# SCH_VRegulator_2024-07-16.net
KiCad netlist of a schematic drawn in EasyEDA
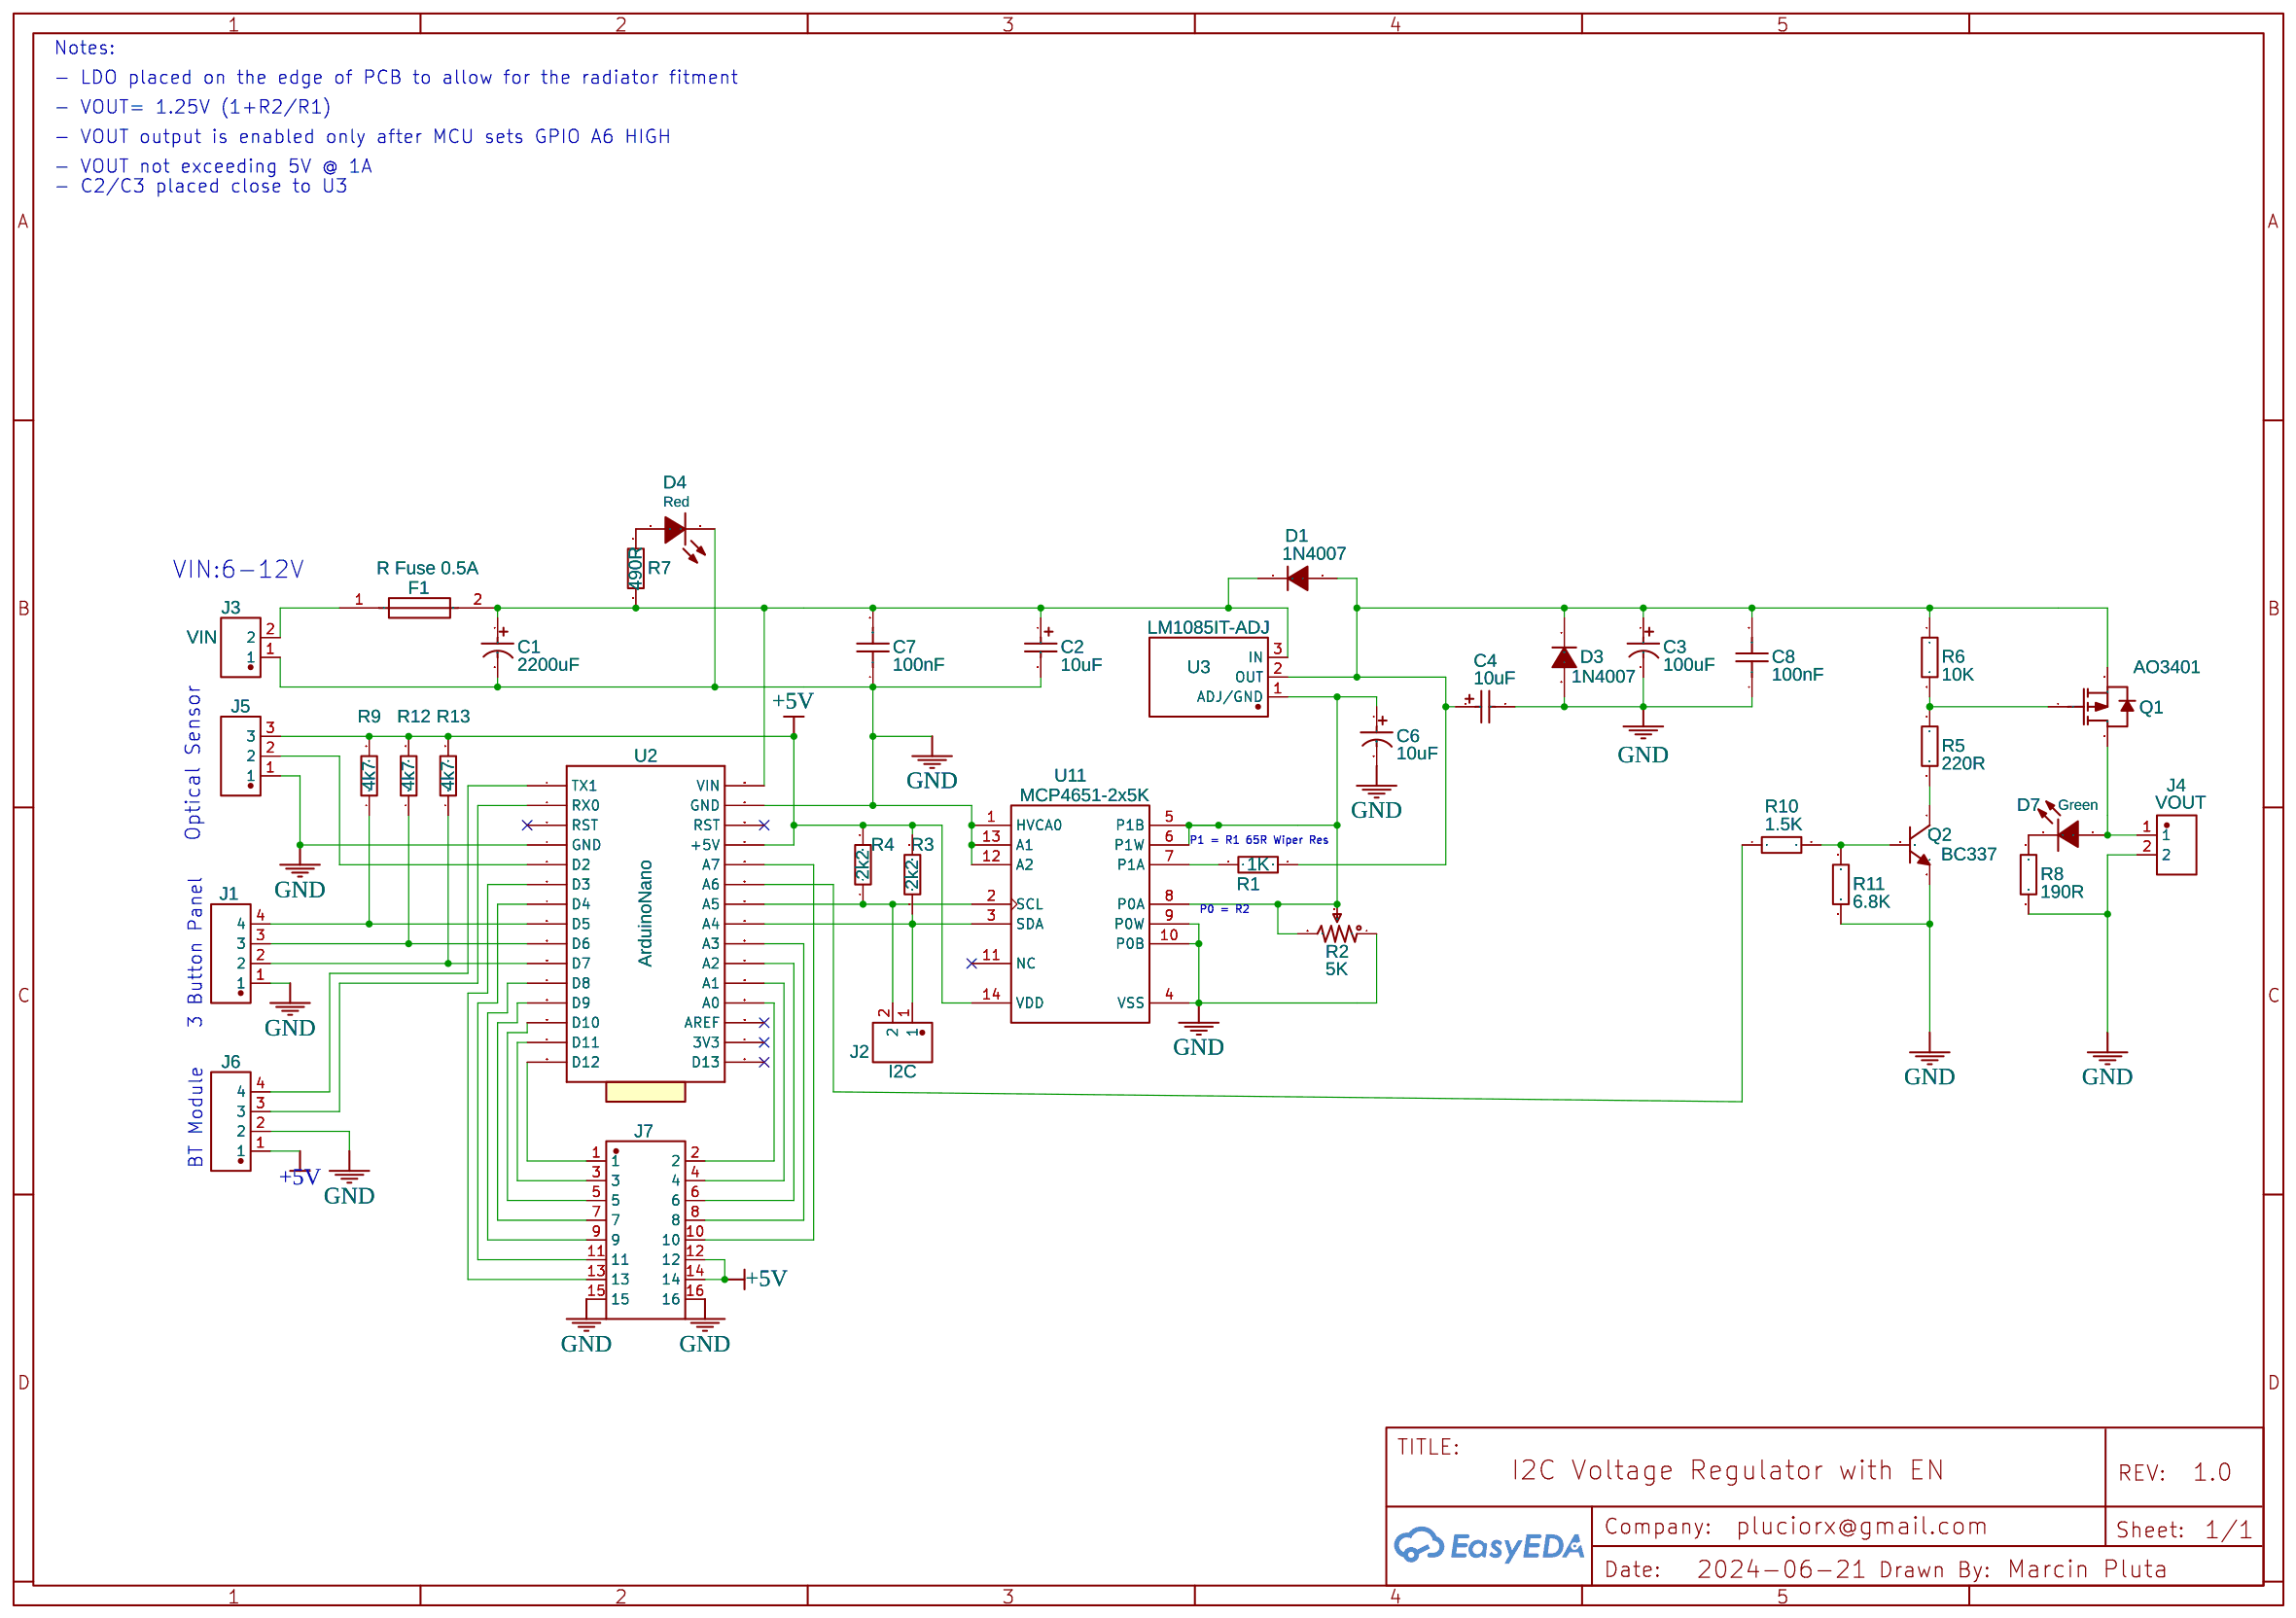
[diagram p0: schematic sheet]

(export (version "E")
  (design (tool "Eeschema 10.0.6"))
  (components
    (comp (ref "C1")
      (value "2200uF")
      (fields
        (field (name "Manufacturer Part") "KM228M025J20RR0VH2FP0")
        (field (name "Manufacturer") "CX(承兴)")
      )
      (libsource (lib "") (part "2200uF 25V 13*20"))
    )
    (comp (ref "C2")
      (value "10uF")
      (fields (field (name "Manufacturer Part") "TAJC106K025RNJ") (field (name "Manufacturer") "Kyocera AVX"))
      (libsource (lib "") (part "TAJC106K025RNJ_1"))
    )
    (comp (ref "C3")
      (value "100uF")
      (fields (field (name "Manufacturer Part") "ERS1EM101E11OT") (field (name "Manufacturer") "AISHI(艾华集团)"))
      (libsource (lib "") (part "ERS1EM101E11OT"))
    )
    (comp (ref "C4")
      (value "10uF")
      (fields (field (name "Manufacturer Part") "TAJC106K025RNJ") (field (name "Manufacturer") "Kyocera AVX"))
      (libsource (lib "") (part "TAJC106K025RNJ"))
    )
    (comp (ref "C6")
      (value "10uF")
      (fields (field (name "Manufacturer Part") "KF100M025C110A") (field (name "Manufacturer") "CapXon(丰宾)"))
      (libsource (lib "") (part "KF100M025C110A"))
    )
    (comp (ref "C7")
      (value "100nF")
      (fields
        (field (name "Manufacturer Part") "CC2A104ZC1ED3F7C1100")
        (field (name "Manufacturer") "Dersonic(德尔创)")
      )
      (libsource (lib "") (part "CC2A104ZC1ED3F7C1100"))
    )
    (comp (ref "C8")
      (value "100nF")
      (fields
        (field (name "Manufacturer Part") "CC2A104ZC1ED3F7C1100")
        (field (name "Manufacturer") "Dersonic(德尔创)")
      )
      (libsource (lib "") (part "CC2A104ZC1ED3F7C1100"))
    )
    (comp (ref "D1")
      (value "1N4007")
      (fields (field (name "Manufacturer") "DYELEC"))
      (libsource (lib "") (part "1N4007_C84179_1"))
    )
    (comp (ref "D3")
      (value "1N4007")
      (fields (field (name "Manufacturer") "DYELEC"))
      (libsource (lib "") (part "1N4007_C84179"))
    )
    (comp (ref "D4")
      (value "Red")
      (fields (field (name "Manufacturer Part") "WP710A10ID") (field (name "Manufacturer") "Kingbright"))
      (libsource (lib "") (part "WP710A10ID"))
    )
    (comp (ref "D7")
      (value "Green")
      (fields (field (name "Manufacturer Part") "WP710A10ID") (field (name "Manufacturer") "Kingbright"))
      (libsource (lib "") (part "WP710A10ID_1"))
    )
    (comp (ref "F1")
      (value "R Fuse 0.5A")
      (fields (field (name "Manufacturer Part") "ResettableFuse-500mA"))
      (libsource (lib "") (part "RESETTABLEFUSE-500MA"))
    )
    (comp (ref "J1")
      (value "DZ254W-11-04-65")
      (fields (field (name "Manufacturer") "DEALON(德艺隆)"))
      (libsource (lib "") (part "DZ254W-11-04-65"))
    )
    (comp (ref "J2")
      (value "I2C")
      (fields
        (field (name "Manufacturer Part") "DB301V-3.5-2P-GN-S")
        (field (name "Manufacturer") "DORABO(地博电气)")
      )
      (libsource (lib "") (part "DB301V-3.5-2P-GN_2"))
    )
    (comp (ref "J3")
      (value "VIN")
      (fields
        (field (name "Manufacturer Part") "DB301V-3.5-2P-GN-S")
        (field (name "Manufacturer") "DORABO(地博电气)")
      )
      (libsource (lib "") (part "DB301V-3.5-2P-GN"))
    )
    (comp (ref "J4")
      (value "VOUT")
      (fields
        (field (name "Manufacturer Part") "DB301V-3.5-2P-GN-S")
        (field (name "Manufacturer") "DORABO(地博电气)")
      )
      (libsource (lib "") (part "DB301V-3.5-2P-GN_1"))
    )
    (comp (ref "J5")
      (value "J5")
      (fields
        (field (name "Manufacturer Part") "DB301V-3.5-3P-GN-S")
        (field (name "Manufacturer") "DORABO(地博电气)")
      )
      (libsource (lib "") (part "DB301V-3.5-3P-GN"))
    )
    (comp (ref "J6")
      (value "A2541HWV-4P_C5176037")
      (fields (field (name "Manufacturer Part") "A2541HWV-4P") (field (name "Manufacturer") "CJT(长江连接器)"))
      (libsource (lib "") (part "A2541HWV-4P_C5176037"))
    )
    (comp (ref "J7")
      (value "MZ254R-22-16-10")
      (fields (field (name "Manufacturer") "DEALON(德艺隆)"))
      (libsource (lib "") (part "MZ254R-22-16-10"))
    )
    (comp (ref "Q1")
      (value "AO3401")
      (fields (field (name "Manufacturer") "YFW(佑风微)"))
      (libsource (lib "") (part "AO3401_C2977510"))
    )
    (comp (ref "Q2")
      (value "BC337")
      (fields (field (name "Manufacturer Part") "BC33740BU") (field (name "Manufacturer") "onsemi(安森美)"))
      (libsource (lib "") (part "BC33740BU"))
    )
    (comp (ref "R1")
      (value "1K")
      (fields (field (name "Manufacturer Part") "MOR01SJ0101A10") (field (name "Manufacturer") "Multicomp"))
      (libsource (lib "") (part "RESISTOR 100 OHM 1W COPY_1"))
    )
    (comp (ref "R2")
      (value "5K")
      (fields (field (name "Manufacturer Part") "3296W-1-502") (field (name "Manufacturer") "BOCHEN(博晨)"))
      (libsource (lib "") (part "3296W-1-502"))
    )
    (comp (ref "R3")
      (value "2k2")
      (fields (field (name "Manufacturer Part") "MOR01SJ0101A10") (field (name "Manufacturer") "Multicomp"))
      (libsource (lib "") (part "RESISTOR 100 OHM 1W COPY"))
    )
    (comp (ref "R4")
      (value "2k2")
      (fields (field (name "Manufacturer Part") "MOR01SJ0101A10") (field (name "Manufacturer") "Multicomp"))
      (libsource (lib "") (part "RESISTOR 100 OHM 1W COPY"))
    )
    (comp (ref "R5")
      (value "220R")
      (fields (field (name "Manufacturer Part") "MOR01SJ0101A10") (field (name "Manufacturer") "Multicomp"))
      (libsource (lib "") (part "RESISTOR 100 OHM 1W COPY_2"))
    )
    (comp (ref "R6")
      (value "10K")
      (fields (field (name "Manufacturer Part") "MOR01SJ0101A10") (field (name "Manufacturer") "Multicomp"))
      (libsource (lib "") (part "RESISTOR 100 OHM 1W COPY_2"))
    )
    (comp (ref "R7")
      (value "490R")
      (fields (field (name "Manufacturer Part") "MOR01SJ0101A10") (field (name "Manufacturer") "Multicomp"))
      (libsource (lib "") (part "RESISTOR 100 OHM 1W COPY_2"))
    )
    (comp (ref "R8")
      (value "190R")
      (fields (field (name "Manufacturer Part") "MOR01SJ0101A10") (field (name "Manufacturer") "Multicomp"))
      (libsource (lib "") (part "RESISTOR 100 OHM 1W COPY_2"))
    )
    (comp (ref "R9")
      (value "4k7")
      (fields (field (name "Manufacturer Part") "MOR01SJ0101A10") (field (name "Manufacturer") "Multicomp"))
      (libsource (lib "") (part "RESISTOR 100 OHM 1W COPY"))
    )
    (comp (ref "R10")
      (value "1.5K")
      (fields (field (name "Manufacturer Part") "MOR01SJ0101A10") (field (name "Manufacturer") "Multicomp"))
      (libsource (lib "") (part "RESISTOR 100 OHM 1W COPY_3"))
    )
    (comp (ref "R11")
      (value "6.8K")
      (fields (field (name "Manufacturer Part") "MOR01SJ0101A10") (field (name "Manufacturer") "Multicomp"))
      (libsource (lib "") (part "RESISTOR 100 OHM 1W COPY"))
    )
    (comp (ref "R12")
      (value "4k7")
      (fields (field (name "Manufacturer Part") "MOR01SJ0101A10") (field (name "Manufacturer") "Multicomp"))
      (libsource (lib "") (part "RESISTOR 100 OHM 1W COPY"))
    )
    (comp (ref "R13")
      (value "4k7")
      (fields (field (name "Manufacturer Part") "MOR01SJ0101A10") (field (name "Manufacturer") "Multicomp"))
      (libsource (lib "") (part "RESISTOR 100 OHM 1W COPY"))
    )
    (comp (ref "U2") (value "ArduinoNano") (libsource (lib "") (part "ArduinoNano_FIX")))
    (comp (ref "U3")
      (value "LM1085IT-ADJ")
      (fields (field (name "Manufacturer Part") "LM1085IT-ADJG") (field (name "Manufacturer") "HGC(深圳汉芯)"))
      (libsource (lib "") (part "LM1085IT-ADJG"))
    )
    (comp (ref "U11")
      (value "MCP4651-2x5K")
      (fields
        (field (name "Manufacturer Part") "MCP4651-103E/ST")
        (field (name "Manufacturer") "MICROCHIP(美国微芯)")
      )
      (libsource (lib "") (part "MCP4651-103E/ST"))
    )
  )
  (nets
    (net (code "1") (name "+5V") (class "Default")
      (node (ref "J5") (pin "3") (pinfunction "3_3") (pintype "unspecified"))
      (node (ref "J6") (pin "1") (pinfunction "1_1") (pintype "unspecified"))
      (node (ref "J7") (pin "12") (pinfunction "12_12") (pintype "unspecified"))
      (node (ref "J7") (pin "14") (pinfunction "14_14") (pintype "unspecified"))
      (node (ref "R12") (pin "2") (pinfunction "2_2") (pintype "unspecified"))
      (node (ref "R13") (pin "2") (pinfunction "2_2") (pintype "unspecified"))
      (node (ref "R3") (pin "2") (pinfunction "2_2") (pintype "unspecified"))
      (node (ref "R4") (pin "2") (pinfunction "2_2") (pintype "unspecified"))
      (node (ref "R9") (pin "2") (pinfunction "2_2") (pintype "unspecified"))
      (node (ref "U11") (pin "14") (pinfunction "VDD_14") (pintype "passive"))
      (node (ref "U2") (pin "27") (pinfunction "+5V_27") (pintype "passive"))
    )
    (net (code "2") (name "GND") (class "Default")
      (node (ref "C1") (pin "2") (pinfunction "2_2") (pintype "input"))
      (node (ref "C2") (pin "2") (pinfunction "2_2") (pintype "input"))
      (node (ref "C3") (pin "2") (pinfunction "2_2") (pintype "input"))
      (node (ref "C4") (pin "2") (pinfunction "2_2") (pintype "input"))
      (node (ref "C6") (pin "2") (pinfunction "2_2") (pintype "input"))
      (node (ref "C7") (pin "1") (pinfunction "1_1") (pintype "unspecified"))
      (node (ref "C8") (pin "1") (pinfunction "1_1") (pintype "unspecified"))
      (node (ref "D3") (pin "2") (pinfunction "A_2") (pintype "unspecified"))
      (node (ref "D4") (pin "2") (pinfunction "K_2") (pintype "unspecified"))
      (node (ref "J1") (pin "1") (pinfunction "1_1") (pintype "unspecified"))
      (node (ref "J3") (pin "1") (pinfunction "1_1") (pintype "unspecified"))
      (node (ref "J4") (pin "2") (pinfunction "2_2") (pintype "unspecified"))
      (node (ref "J5") (pin "1") (pinfunction "1_1") (pintype "unspecified"))
      (node (ref "J6") (pin "2") (pinfunction "2_2") (pintype "unspecified"))
      (node (ref "J7") (pin "15") (pinfunction "15_15") (pintype "unspecified"))
      (node (ref "J7") (pin "16") (pinfunction "16_16") (pintype "unspecified"))
      (node (ref "Q2") (pin "3") (pinfunction "E_3") (pintype "input"))
      (node (ref "R11") (pin "1") (pinfunction "1_1") (pintype "unspecified"))
      (node (ref "R2") (pin "1") (pinfunction "1_1") (pintype "unspecified"))
      (node (ref "R8") (pin "2") (pinfunction "2_2") (pintype "unspecified"))
      (node (ref "U11") (pin "1") (pinfunction "HVCA0_1") (pintype "unspecified"))
      (node (ref "U11") (pin "10") (pinfunction "P0B_10") (pintype "unspecified"))
      (node (ref "U11") (pin "12") (pinfunction "A2_12") (pintype "unspecified"))
      (node (ref "U11") (pin "13") (pinfunction "A1_13") (pintype "unspecified"))
      (node (ref "U11") (pin "4") (pinfunction "VSS_4") (pintype "passive"))
      (node (ref "U11") (pin "9") (pinfunction "P0W_9") (pintype "unspecified"))
      (node (ref "U2") (pin "29") (pinfunction "GND_29") (pintype "passive"))
      (node (ref "U2") (pin "4") (pinfunction "GND_4") (pintype "passive"))
    )
    (net (code "3") (name "Net-(D1-A)") (class "Default")
      (node (ref "C3") (pin "1") (pinfunction "1_1") (pintype "input"))
      (node (ref "C4") (pin "1") (pinfunction "1_1") (pintype "input"))
      (node (ref "C8") (pin "2") (pinfunction "2_2") (pintype "unspecified"))
      (node (ref "D1") (pin "2") (pinfunction "A_2") (pintype "unspecified"))
      (node (ref "D3") (pin "1") (pinfunction "C_1") (pintype "unspecified"))
      (node (ref "Q1") (pin "2") (pinfunction "S_2") (pintype "unspecified"))
      (node (ref "R1") (pin "1") (pinfunction "1_1") (pintype "unspecified"))
      (node (ref "R6") (pin "1") (pinfunction "1_1") (pintype "unspecified"))
      (node (ref "U3") (pin "2") (pinfunction "OUT_2") (pintype "unspecified"))
    )
    (net (code "4") (name "Net-(D1-C)") (class "Default")
      (node (ref "C1") (pin "1") (pinfunction "1_1") (pintype "input"))
      (node (ref "C2") (pin "1") (pinfunction "1_1") (pintype "input"))
      (node (ref "C7") (pin "2") (pinfunction "2_2") (pintype "unspecified"))
      (node (ref "D1") (pin "1") (pinfunction "C_1") (pintype "unspecified"))
      (node (ref "F1") (pin "2") (pinfunction "2_2") (pintype "unspecified"))
      (node (ref "R7") (pin "2") (pinfunction "2_2") (pintype "unspecified"))
      (node (ref "U2") (pin "30") (pinfunction "VIN_30") (pintype "passive"))
      (node (ref "U3") (pin "3") (pinfunction "IN_3") (pintype "unspecified"))
    )
    (net (code "5") (name "Net-(D4-A)") (class "Default")
      (node (ref "D4") (pin "1") (pinfunction "A_1") (pintype "unspecified"))
      (node (ref "R7") (pin "1") (pinfunction "1_1") (pintype "unspecified"))
    )
    (net (code "6") (name "Net-(D7-A)") (class "Default")
      (node (ref "D7") (pin "1") (pinfunction "A_1") (pintype "unspecified"))
      (node (ref "J4") (pin "1") (pinfunction "1_1") (pintype "unspecified"))
      (node (ref "Q1") (pin "3") (pinfunction "D_3") (pintype "unspecified"))
    )
    (net (code "7") (name "Net-(D7-K)") (class "Default")
      (node (ref "D7") (pin "2") (pinfunction "K_2") (pintype "unspecified"))
      (node (ref "R8") (pin "1") (pinfunction "1_1") (pintype "unspecified"))
    )
    (net (code "8") (name "Net-(F1-Pad1)") (class "Default")
      (node (ref "F1") (pin "1") (pinfunction "1_1") (pintype "unspecified"))
      (node (ref "J3") (pin "2") (pinfunction "2_2") (pintype "unspecified"))
    )
    (net (code "9") (name "Net-(Q1-G)") (class "Default")
      (node (ref "Q1") (pin "1") (pinfunction "G_1") (pintype "unspecified"))
      (node (ref "R5") (pin "1") (pinfunction "1_1") (pintype "unspecified"))
      (node (ref "R6") (pin "2") (pinfunction "2_2") (pintype "unspecified"))
    )
    (net (code "10") (name "Net-(Q2-B)") (class "Default")
      (node (ref "Q2") (pin "2") (pinfunction "B_2") (pintype "input"))
      (node (ref "R10") (pin "2") (pinfunction "2_2") (pintype "unspecified"))
      (node (ref "R11") (pin "2") (pinfunction "2_2") (pintype "unspecified"))
    )
    (net (code "11") (name "Net-(Q2-C)") (class "Default")
      (node (ref "Q2") (pin "1") (pinfunction "C_1") (pintype "input"))
      (node (ref "R5") (pin "2") (pinfunction "2_2") (pintype "unspecified"))
    )
    (net (code "12") (name "Net-(U2-A0)") (class "Default")
      (node (ref "J7") (pin "2") (pinfunction "2_2") (pintype "unspecified"))
      (node (ref "U2") (pin "19") (pinfunction "A0_19") (pintype "input"))
    )
    (net (code "13") (name "Net-(U2-A1)") (class "Default")
      (node (ref "J7") (pin "4") (pinfunction "4_4") (pintype "unspecified"))
      (node (ref "U2") (pin "20") (pinfunction "A1_20") (pintype "input"))
    )
    (net (code "14") (name "Net-(U2-A2)") (class "Default")
      (node (ref "J7") (pin "6") (pinfunction "6_6") (pintype "unspecified"))
      (node (ref "U2") (pin "21") (pinfunction "A2_21") (pintype "input"))
    )
    (net (code "15") (name "Net-(U2-A3)") (class "Default")
      (node (ref "J7") (pin "8") (pinfunction "8_8") (pintype "unspecified"))
      (node (ref "U2") (pin "22") (pinfunction "A3_22") (pintype "input"))
    )
    (net (code "16") (name "Net-(U2-A6)") (class "Default")
      (node (ref "R10") (pin "1") (pinfunction "1_1") (pintype "unspecified"))
      (node (ref "U2") (pin "25") (pinfunction "A6_25") (pintype "input"))
    )
    (net (code "17") (name "Net-(U2-A7)") (class "Default")
      (node (ref "J7") (pin "10") (pinfunction "10_10") (pintype "unspecified"))
      (node (ref "U2") (pin "26") (pinfunction "A7_26") (pintype "input"))
    )
    (net (code "18") (name "Net-(U2-D2)") (class "Default")
      (node (ref "J5") (pin "2") (pinfunction "2_2") (pintype "unspecified"))
      (node (ref "U2") (pin "5") (pinfunction "D2_5") (pintype "bidirectional"))
    )
    (net (code "19") (name "Net-(U2-D3)") (class "Default")
      (node (ref "J7") (pin "13") (pinfunction "13_13") (pintype "unspecified"))
      (node (ref "U2") (pin "6") (pinfunction "D3_6") (pintype "bidirectional"))
    )
    (net (code "20") (name "Net-(U2-D4)") (class "Default")
      (node (ref "J7") (pin "11") (pinfunction "11_11") (pintype "unspecified"))
      (node (ref "U2") (pin "7") (pinfunction "D4_7") (pintype "bidirectional"))
    )
    (net (code "21") (name "Net-(U2-D5)") (class "Default")
      (node (ref "J1") (pin "4") (pinfunction "4_4") (pintype "unspecified"))
      (node (ref "R9") (pin "1") (pinfunction "1_1") (pintype "unspecified"))
      (node (ref "U2") (pin "8") (pinfunction "D5_8") (pintype "bidirectional"))
    )
    (net (code "22") (name "Net-(U2-D6)") (class "Default")
      (node (ref "J1") (pin "3") (pinfunction "3_3") (pintype "unspecified"))
      (node (ref "R12") (pin "1") (pinfunction "1_1") (pintype "unspecified"))
      (node (ref "U2") (pin "9") (pinfunction "D6_9") (pintype "bidirectional"))
    )
    (net (code "23") (name "Net-(U2-D7)") (class "Default")
      (node (ref "J1") (pin "2") (pinfunction "2_2") (pintype "unspecified"))
      (node (ref "R13") (pin "1") (pinfunction "1_1") (pintype "unspecified"))
      (node (ref "U2") (pin "10") (pinfunction "D7_10") (pintype "bidirectional"))
    )
    (net (code "24") (name "Net-(U2-D8)") (class "Default")
      (node (ref "J7") (pin "9") (pinfunction "9_9") (pintype "unspecified"))
      (node (ref "U2") (pin "11") (pinfunction "D8_11") (pintype "bidirectional"))
    )
    (net (code "25") (name "Net-(U2-D9)") (class "Default")
      (node (ref "J7") (pin "7") (pinfunction "7_7") (pintype "unspecified"))
      (node (ref "U2") (pin "12") (pinfunction "D9_12") (pintype "bidirectional"))
    )
    (net (code "26") (name "Net-(U2-D10)") (class "Default")
      (node (ref "J7") (pin "5") (pinfunction "5_5") (pintype "unspecified"))
      (node (ref "U2") (pin "13") (pinfunction "D10_13") (pintype "bidirectional"))
    )
    (net (code "27") (name "Net-(U2-D11)") (class "Default")
      (node (ref "J7") (pin "3") (pinfunction "3_3") (pintype "unspecified"))
      (node (ref "U2") (pin "14") (pinfunction "D11_14") (pintype "bidirectional"))
    )
    (net (code "28") (name "Net-(U2-D12)") (class "Default")
      (node (ref "J7") (pin "1") (pinfunction "1_1") (pintype "unspecified"))
      (node (ref "U2") (pin "15") (pinfunction "D12_15") (pintype "bidirectional"))
    )
    (net (code "29") (name "Net-(U2-RX0)") (class "Default")
      (node (ref "J6") (pin "3") (pinfunction "3_3") (pintype "unspecified"))
      (node (ref "U2") (pin "2") (pinfunction "RX0_2") (pintype "input"))
    )
    (net (code "30") (name "Net-(U2-TX1)") (class "Default")
      (node (ref "J6") (pin "4") (pinfunction "4_4") (pintype "unspecified"))
      (node (ref "U2") (pin "1") (pinfunction "TX1_1") (pintype "output"))
    )
    (net (code "31") (name "Net-(U11-P0A)") (class "Default")
      (node (ref "C6") (pin "1") (pinfunction "1_1") (pintype "input"))
      (node (ref "R2") (pin "2") (pinfunction "2_2") (pintype "unspecified"))
      (node (ref "R2") (pin "3") (pinfunction "3_3") (pintype "unspecified"))
      (node (ref "U11") (pin "5") (pinfunction "P1B_5") (pintype "unspecified"))
      (node (ref "U11") (pin "6") (pinfunction "P1W_6") (pintype "unspecified"))
      (node (ref "U11") (pin "8") (pinfunction "P0A_8") (pintype "unspecified"))
      (node (ref "U3") (pin "1") (pinfunction "ADJ/GND_1") (pintype "unspecified"))
    )
    (net (code "32") (name "Net-(U11-P1A)") (class "Default")
      (node (ref "R1") (pin "2") (pinfunction "2_2") (pintype "unspecified"))
      (node (ref "U11") (pin "7") (pinfunction "P1A_7") (pintype "unspecified"))
    )
    (net (code "33") (name "Net-(U11-SCL)") (class "Default")
      (node (ref "J2") (pin "2") (pinfunction "2_2") (pintype "unspecified"))
      (node (ref "R4") (pin "1") (pinfunction "1_1") (pintype "unspecified"))
      (node (ref "U11") (pin "2") (pinfunction "SCL_2") (pintype "unspecified"))
      (node (ref "U2") (pin "24") (pinfunction "A5_24") (pintype "input"))
    )
    (net (code "34") (name "Net-(U11-SDA)") (class "Default")
      (node (ref "J2") (pin "1") (pinfunction "1_1") (pintype "unspecified"))
      (node (ref "R3") (pin "1") (pinfunction "1_1") (pintype "unspecified"))
      (node (ref "U11") (pin "3") (pinfunction "SDA_3") (pintype "bidirectional"))
      (node (ref "U2") (pin "23") (pinfunction "A4_23") (pintype "input"))
    )
    (net (code "35") (name "unconnected-(U2-3V3-Pad17)") (class "Default")
      (node (ref "U2") (pin "17") (pinfunction "3V3_17") (pintype "passive+no_connect"))
    )
    (net (code "36") (name "unconnected-(U2-AREF-Pad18)") (class "Default")
      (node (ref "U2") (pin "18") (pinfunction "AREF_18") (pintype "passive+no_connect"))
    )
    (net (code "37") (name "unconnected-(U2-D13-Pad16)") (class "Default")
      (node (ref "U2") (pin "16") (pinfunction "D13_16") (pintype "bidirectional+no_connect"))
    )
    (net (code "38") (name "unconnected-(U2-RST-Pad3)") (class "Default")
      (node (ref "U2") (pin "3") (pinfunction "RST_3") (pintype "input+no_connect"))
    )
    (net (code "39") (name "unconnected-(U2-RST-Pad28)") (class "Default")
      (node (ref "U2") (pin "28") (pinfunction "RST_28") (pintype "bidirectional+no_connect"))
    )
    (net (code "40") (name "unconnected-(U11-NC-Pad11)") (class "Default")
      (node (ref "U11") (pin "11") (pinfunction "NC_11") (pintype "unspecified+no_connect"))
    )
  )
)
